# LevelConverter.net
KiCad netlist of a schematic drawn in Altium Designer
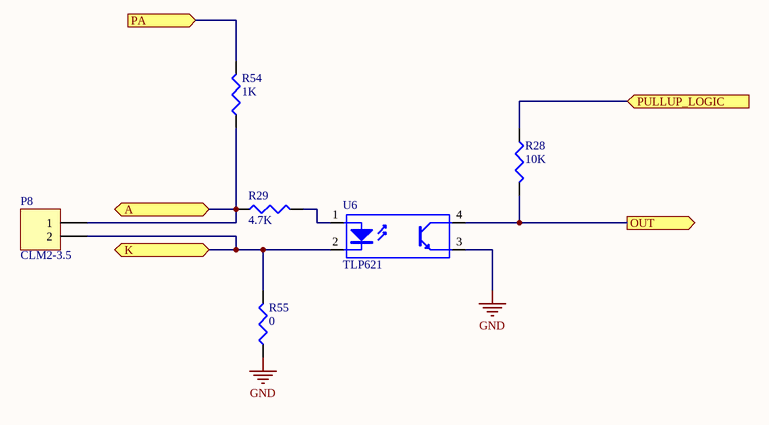
[diagram p0: LevelConverter.SchDoc]

(export (version "E")
  (design (tool "Eeschema 10.0.6"))
  (components
    (comp (ref "P8")
      (value "CLM2-3.5")
      (footprint "CLM2-3.5")
      (libsource (lib "connectors") (part "CLM2-3.5"))
    )
    (comp (ref "R28")
      (value "10K")
      (footprint "R2012[0805]")
      (description "R0805")
      (fields (field (name "PUBLISHER") "Altium Limited"))
      (libsource (lib "ResAndCaps") (part "R0805"))
    )
    (comp (ref "R29")
      (value "4.7K")
      (footprint "R2012[0805]")
      (description "R0805")
      (fields (field (name "PUBLISHER") "Altium Limited"))
      (libsource (lib "ResAndCaps") (part "R0805"))
    )
    (comp (ref "R54")
      (value "1K")
      (footprint "R2012[0805]")
      (description "R0805")
      (fields (field (name "PUBLISHER") "Altium Limited"))
      (libsource (lib "ResAndCaps") (part "R0805"))
    )
    (comp (ref "R55")
      (value "0")
      (footprint "R2012[0805]")
      (description "R0805")
      (fields (field (name "PUBLISHER") "Altium Limited"))
      (libsource (lib "ResAndCaps") (part "R0805"))
    )
    (comp (ref "U6") (value "TLP621") (footprint "DIP4") (libsource (lib "optocoupler") (part "TLP621")))
  )
  (nets
    (net (code "1") (name "/A") (class "Default")
      (node (ref "P8") (pin "1") (pinfunction "1_1") (pintype "passive"))
      (node (ref "R29") (pin "1") (pinfunction "1_1") (pintype "passive"))
      (node (ref "R54") (pin "1") (pinfunction "1_1") (pintype "passive"))
    )
    (net (code "2") (name "/K") (class "Default")
      (node (ref "P8") (pin "2") (pinfunction "2_2") (pintype "passive"))
      (node (ref "R55") (pin "2") (pinfunction "2_2") (pintype "passive"))
      (node (ref "U6") (pin "2") (pinfunction "K_2") (pintype "passive"))
    )
    (net (code "3") (name "/OUT") (class "Default")
      (node (ref "R28") (pin "2") (pinfunction "2_2") (pintype "passive"))
      (node (ref "U6") (pin "4") (pinfunction "C_4") (pintype "passive"))
    )
    (net (code "4") (name "/PA") (class "Default")
      (node (ref "R54") (pin "2") (pinfunction "2_2") (pintype "passive"))
    )
    (net (code "5") (name "/PULLUP_LOGIC") (class "Default")
      (node (ref "R28") (pin "1") (pinfunction "1_1") (pintype "passive"))
    )
    (net (code "6") (name "GND") (class "Default")
      (node (ref "R55") (pin "1") (pinfunction "1_1") (pintype "passive"))
      (node (ref "U6") (pin "3") (pinfunction "E_3") (pintype "passive"))
    )
    (net (code "7") (name "Net-(U6-A)") (class "Default")
      (node (ref "R29") (pin "2") (pinfunction "2_2") (pintype "passive"))
      (node (ref "U6") (pin "1") (pinfunction "A_1") (pintype "passive"))
    )
  )
)
